# LCmeter0-LCD3310-8pinlcd-PIC-COMP.net
KiCad netlist of a schematic drawn in EAGLE
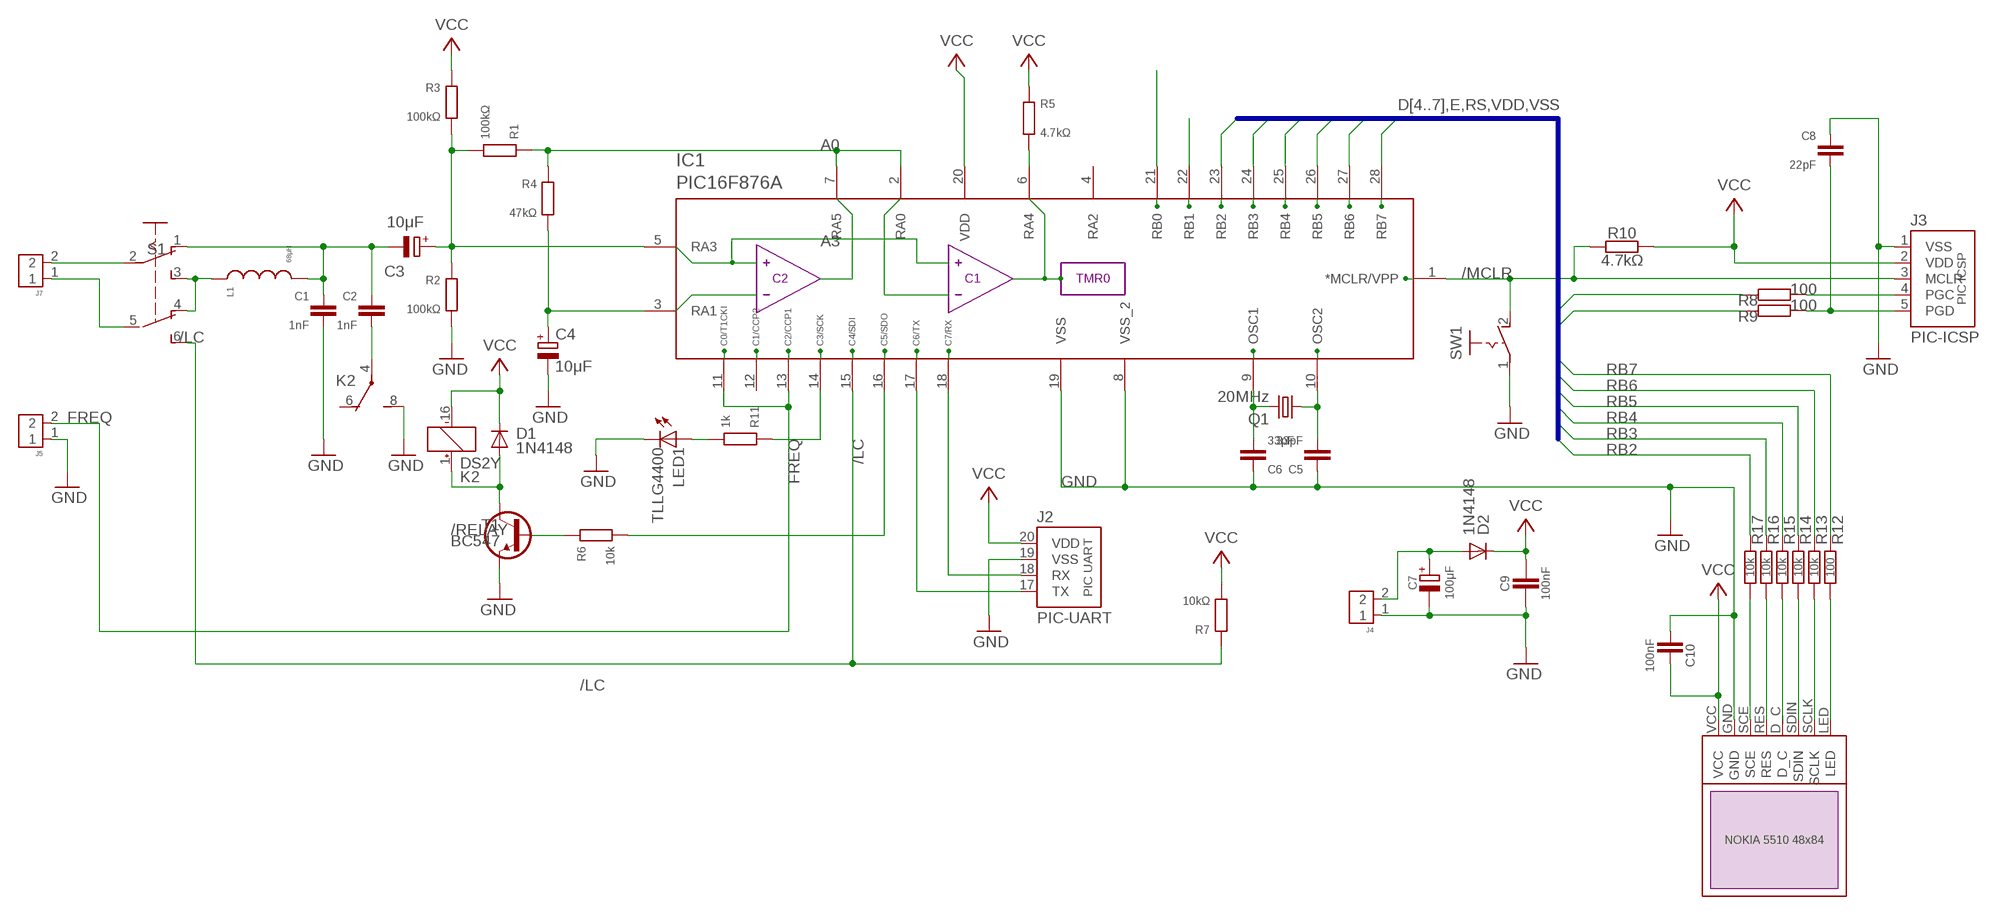
[diagram p0: schematic, sheet 1]

(export (version "E")
  (design (tool "Eeschema 10.0.6"))
  (components
    (comp (ref "C1")
      (value "1nF")
      (footprint "eagle-import:C050-025X060")
      (libsource (lib "eagle-import") (part "C025-025X060"))
    )
    (comp (ref "C2")
      (value "1nF")
      (footprint "eagle-import:C050-025X060")
      (libsource (lib "eagle-import") (part "C025-025X060"))
    )
    (comp (ref "C3")
      (value "10μF")
      (footprint "eagle-import:E2,5-4")
      (libsource (lib "eagle-import") (part "CPOLE2,5-4"))
    )
    (comp (ref "C4")
      (value "10μF")
      (footprint "eagle-import:E2,5-4")
      (libsource (lib "eagle-import") (part "CPOLE2,5-4"))
    )
    (comp (ref "C5")
      (value "33pF")
      (footprint "eagle-import:C025-020X036")
      (libsource (lib "eagle-import") (part "C025-020X036"))
    )
    (comp (ref "C6")
      (value "33pF")
      (footprint "eagle-import:C025-020X036")
      (libsource (lib "eagle-import") (part "C025-020X036"))
    )
    (comp (ref "C7")
      (value "100μF")
      (footprint "eagle-import:E5-5")
      (libsource (lib "eagle-import") (part "CPOLE5-5"))
    )
    (comp (ref "C8")
      (value "22pF")
      (footprint "eagle-import:C050-020X036")
      (libsource (lib "eagle-import") (part "C050-020X036"))
    )
    (comp (ref "C9")
      (value "100nF")
      (footprint "eagle-import:C025-024X044")
      (libsource (lib "eagle-import") (part "C-EU025-024X044"))
    )
    (comp (ref "C10")
      (value "100nF")
      (footprint "eagle-import:C025-015X024_V")
      (libsource (lib "eagle-import") (part "C025-015X024"))
    )
    (comp (ref "D1")
      (value "1N4148")
      (footprint "eagle-import:DO34-7")
      (libsource (lib "eagle-import") (part "1N414834-7"))
    )
    (comp (ref "D2")
      (value "1N4148")
      (footprint "eagle-import:DO34-10V")
      (libsource (lib "eagle-import") (part "1N414834-10V"))
    )
    (comp (ref "IC1")
      (value "PIC16F876A")
      (footprint "eagle-import:DIL28-3_V")
      (libsource (lib "eagle-import") (part "PIC16F876A-X/SP-COMPDIL28-3/V"))
    )
    (comp (ref "J2")
      (value "PIC-UART")
      (footprint "eagle-import:PIC-UART")
      (libsource (lib "eagle-import") (part "PIC-UART"))
    )
    (comp (ref "J3")
      (value "PIC-ICSP")
      (footprint "eagle-import:PIC-ICSP")
      (libsource (lib "eagle-import") (part "PIC-ICSPICSP"))
    )
    (comp (ref "J4")
      (value "J4")
      (footprint "eagle-import:CONN-2P")
      (libsource (lib "eagle-import") (part "CONN-2P2P/H"))
    )
    (comp (ref "J5")
      (value "CONN-2P2P/V")
      (footprint "eagle-import:CONN-2P-V")
      (libsource (lib "eagle-import") (part "CONN-2P2P/V"))
    )
    (comp (ref "J6")
      (value "NOKIA-5510-48X84")
      (footprint "eagle-import:CONN-LCD5510")
      (libsource (lib "eagle-import") (part "NOKIA-5510-48X84"))
    )
    (comp (ref "J7")
      (value "CONN-2P2P/V")
      (footprint "eagle-import:CONN-2P-V")
      (libsource (lib "eagle-import") (part "CONN-2P2P/V"))
    )
    (comp (ref "K2")
      (value "DS2Y")
      (footprint "eagle-import:DS2Y")
      (fields (field (name "MPN") "DS2Y-S-DC5V"))
      (libsource (lib "eagle-import") (part "DS2Y-S-DC5V"))
    )
    (comp (ref "L1")
      (value "68μH")
      (footprint "eagle-import:L-09R")
      (libsource (lib "eagle-import") (part "L-09R"))
    )
    (comp (ref "LED1")
      (value "TLLG4400")
      (footprint "eagle-import:LED3MM")
      (fields (field (name "MF") "VISHAY SEMICONDUCTOR"))
      (libsource (lib "eagle-import") (part "TLLG4400"))
    )
    (comp (ref "Q1")
      (value "20MHz")
      (footprint "eagle-import:HC49")
      (libsource (lib "eagle-import") (part "CRYSTALHC49"))
    )
    (comp (ref "R1")
      (value "100kΩ")
      (footprint "eagle-import:0202_7")
      (libsource (lib "eagle-import") (part "R0202/7"))
    )
    (comp (ref "R2")
      (value "100kΩ")
      (footprint "eagle-import:0202_7")
      (libsource (lib "eagle-import") (part "R0202/7"))
    )
    (comp (ref "R3")
      (value "100kΩ")
      (footprint "eagle-import:0202_7")
      (libsource (lib "eagle-import") (part "R0202/7"))
    )
    (comp (ref "R4")
      (value "47kΩ")
      (footprint "eagle-import:0202_7")
      (libsource (lib "eagle-import") (part "R0202/7"))
    )
    (comp (ref "R5")
      (value "4.7kΩ")
      (footprint "eagle-import:0202_7")
      (libsource (lib "eagle-import") (part "R0202/7"))
    )
    (comp (ref "R6")
      (value "10k")
      (footprint "eagle-import:0202_7-V")
      (libsource (lib "eagle-import") (part "R0202/7-V"))
    )
    (comp (ref "R7")
      (value "10kΩ")
      (footprint "eagle-import:0202_10-V")
      (libsource (lib "eagle-import") (part "R0202/10-V"))
    )
    (comp (ref "R8")
      (value "100")
      (footprint "eagle-import:0202_7")
      (libsource (lib "eagle-import") (part "R0202/7"))
    )
    (comp (ref "R9")
      (value "100")
      (footprint "eagle-import:0202_2V")
      (libsource (lib "eagle-import") (part "R0202/2V"))
    )
    (comp (ref "R10")
      (value "4.7kΩ")
      (footprint "eagle-import:0202_7")
      (libsource (lib "eagle-import") (part "R0202/7"))
    )
    (comp (ref "R11")
      (value "1k")
      (footprint "eagle-import:0202_5-V")
      (libsource (lib "eagle-import") (part "R0202/5-V"))
    )
    (comp (ref "R12")
      (value "100")
      (footprint "eagle-import:0202_7")
      (libsource (lib "eagle-import") (part "R0202/7"))
    )
    (comp (ref "R13")
      (value "10k")
      (footprint "eagle-import:0202_7")
      (libsource (lib "eagle-import") (part "R0202/7"))
    )
    (comp (ref "R14")
      (value "10k")
      (footprint "eagle-import:0202_7")
      (libsource (lib "eagle-import") (part "R0202/7"))
    )
    (comp (ref "R15")
      (value "10k")
      (footprint "eagle-import:0202_7")
      (libsource (lib "eagle-import") (part "R0202/7"))
    )
    (comp (ref "R16")
      (value "10k")
      (footprint "eagle-import:0202_7")
      (libsource (lib "eagle-import") (part "R0202/7"))
    )
    (comp (ref "R17")
      (value "10k")
      (footprint "eagle-import:0202_7")
      (libsource (lib "eagle-import") (part "R0202/7"))
    )
    (comp (ref "S1")
      (value "SL-SW-2P-2T-H")
      (footprint "eagle-import:SLSW-2P2T-H")
      (libsource (lib "eagle-import") (part "SL-SW-2P-2T-H"))
    )
    (comp (ref "SW1")
      (value "PB-1P-1T")
      (footprint "eagle-import:PB-1P1T")
      (libsource (lib "eagle-import") (part "PB-1P-1T"))
    )
    (comp (ref "T1")
      (value "BC547")
      (footprint "eagle-import:TO92-CBE-A")
      (libsource (lib "eagle-import") (part "BC547CBE-A"))
    )
  )
  (nets
    (net (code "5") (name "/A0") (class "Default")
      (node (ref "IC1") (pin "2") (pinfunction "RA0_2") (pintype "passive"))
      (node (ref "IC1") (pin "7") (pinfunction "RA5_7") (pintype "passive"))
      (node (ref "R1") (pin "2") (pinfunction "2_2") (pintype "passive"))
      (node (ref "R4") (pin "2") (pinfunction "2_2") (pintype "passive"))
    )
    (net (code "6") (name "/A3") (class "Default")
      (node (ref "C3") (pin "+") (pinfunction "+_+") (pintype "passive"))
      (node (ref "IC1") (pin "5") (pinfunction "RA3_5") (pintype "passive"))
      (node (ref "R1") (pin "1") (pinfunction "1_1") (pintype "passive"))
      (node (ref "R2") (pin "2") (pinfunction "2_2") (pintype "passive"))
      (node (ref "R3") (pin "1") (pinfunction "1_1") (pintype "passive"))
    )
    (net (code "7") (name "/FREQ") (class "Default")
      (node (ref "IC1") (pin "11") (pinfunction "RC0_11") (pintype "passive"))
      (node (ref "IC1") (pin "13") (pinfunction "RC2_13") (pintype "passive"))
      (node (ref "J5") (pin "2") (pinfunction "2_2") (pintype "bidirectional"))
    )
    (net (code "8") (name "/RB2") (class "Default")
      (node (ref "IC1") (pin "23") (pinfunction "RB2_23") (pintype "passive"))
      (node (ref "R17") (pin "2") (pinfunction "2_2") (pintype "passive"))
    )
    (net (code "9") (name "/RB3") (class "Default")
      (node (ref "IC1") (pin "24") (pinfunction "RB3_24") (pintype "passive"))
      (node (ref "R16") (pin "2") (pinfunction "2_2") (pintype "passive"))
    )
    (net (code "10") (name "/RB4") (class "Default")
      (node (ref "IC1") (pin "25") (pinfunction "RB4_25") (pintype "passive"))
      (node (ref "R15") (pin "2") (pinfunction "2_2") (pintype "passive"))
    )
    (net (code "11") (name "/RB5") (class "Default")
      (node (ref "IC1") (pin "26") (pinfunction "RB5_26") (pintype "passive"))
      (node (ref "R14") (pin "2") (pinfunction "2_2") (pintype "passive"))
    )
    (net (code "12") (name "/RB6") (class "Default")
      (node (ref "IC1") (pin "27") (pinfunction "RB6_27") (pintype "passive"))
      (node (ref "R13") (pin "2") (pinfunction "2_2") (pintype "passive"))
      (node (ref "R8") (pin "2") (pinfunction "2_2") (pintype "passive"))
    )
    (net (code "13") (name "/RB7") (class "Default")
      (node (ref "IC1") (pin "28") (pinfunction "RB7_28") (pintype "passive"))
      (node (ref "R12") (pin "2") (pinfunction "2_2") (pintype "passive"))
      (node (ref "R9") (pin "2") (pinfunction "2_2") (pintype "passive"))
    )
    (net (code "15") (name "/{slash}LC") (class "Default")
      (node (ref "IC1") (pin "15") (pinfunction "RC4_15") (pintype "passive"))
      (node (ref "R7") (pin "2") (pinfunction "2_2") (pintype "passive"))
      (node (ref "S1") (pin "6") (pinfunction "S1_6") (pintype "passive"))
    )
    (net (code "16") (name "/{slash}MCLR") (class "Default")
      (node (ref "IC1") (pin "1") (pinfunction "*MCLR/VPP_1") (pintype "passive"))
      (node (ref "J3") (pin "3") (pinfunction "MCLR_3") (pintype "passive"))
      (node (ref "R10") (pin "2") (pinfunction "2_2") (pintype "passive"))
      (node (ref "SW1") (pin "2") (pinfunction "S_2") (pintype "passive"))
    )
    (net (code "17") (name "/{slash}RELAY") (class "Default")
      (node (ref "D1") (pin "A") (pinfunction "A_A") (pintype "passive"))
      (node (ref "K2") (pin "1") (pinfunction "+_1") (pintype "passive"))
      (node (ref "T1") (pin "C") (pinfunction "C_C") (pintype "passive"))
    )
    (net (code "18") (name "GND") (class "Default")
      (node (ref "C1") (pin "2") (pinfunction "2_2") (pintype "passive"))
      (node (ref "C10") (pin "1") (pinfunction "1_1") (pintype "passive"))
      (node (ref "C4") (pin "-") (pinfunction "-_-") (pintype "passive"))
      (node (ref "C5") (pin "1") (pinfunction "1_1") (pintype "passive"))
      (node (ref "C6") (pin "1") (pinfunction "1_1") (pintype "passive"))
      (node (ref "C7") (pin "-") (pinfunction "-_-") (pintype "passive"))
      (node (ref "C8") (pin "1") (pinfunction "1_1") (pintype "passive"))
      (node (ref "C9") (pin "2") (pinfunction "2_2") (pintype "passive"))
      (node (ref "IC1") (pin "19") (pinfunction "VSS_19") (pintype "passive"))
      (node (ref "IC1") (pin "8") (pinfunction "VSS_2_8") (pintype "passive"))
      (node (ref "J2") (pin "19") (pinfunction "VSS_19") (pintype "passive"))
      (node (ref "J3") (pin "1") (pinfunction "VSS_1") (pintype "passive"))
      (node (ref "J4") (pin "1") (pinfunction "1_1") (pintype "bidirectional"))
      (node (ref "J5") (pin "1") (pinfunction "1_1") (pintype "bidirectional"))
      (node (ref "J6") (pin "GND") (pinfunction "GND_GND") (pintype "passive"))
      (node (ref "K2") (pin "8") (pinfunction "S_8") (pintype "passive"))
      (node (ref "LED1") (pin "K") (pinfunction "C_K") (pintype "passive"))
      (node (ref "R2") (pin "1") (pinfunction "1_1") (pintype "passive"))
      (node (ref "SW1") (pin "1") (pinfunction "P_1") (pintype "passive"))
      (node (ref "T1") (pin "E") (pinfunction "E_E") (pintype "passive"))
    )
    (net (code "19") (name "Net-(C7-Pad+)") (class "Default")
      (node (ref "C7") (pin "+") (pinfunction "+_+") (pintype "passive"))
      (node (ref "D2") (pin "A") (pinfunction "A_A") (pintype "passive"))
      (node (ref "J4") (pin "2") (pinfunction "2_2") (pintype "bidirectional"))
    )
    (net (code "20") (name "Net-(IC1-OSC1)") (class "Default")
      (node (ref "C6") (pin "2") (pinfunction "2_2") (pintype "passive"))
      (node (ref "IC1") (pin "9") (pinfunction "OSC1_9") (pintype "passive"))
      (node (ref "Q1") (pin "2") (pinfunction "2_2") (pintype "passive"))
    )
    (net (code "21") (name "Net-(IC1-OSC2)") (class "Default")
      (node (ref "C5") (pin "2") (pinfunction "2_2") (pintype "passive"))
      (node (ref "IC1") (pin "10") (pinfunction "OSC2_10") (pintype "passive"))
      (node (ref "Q1") (pin "1") (pinfunction "1_1") (pintype "passive"))
    )
    (net (code "22") (name "Net-(IC1-RA1)") (class "Default")
      (node (ref "C4") (pin "+") (pinfunction "+_+") (pintype "passive"))
      (node (ref "IC1") (pin "3") (pinfunction "RA1_3") (pintype "passive"))
      (node (ref "R4") (pin "1") (pinfunction "1_1") (pintype "passive"))
    )
    (net (code "23") (name "Net-(IC1-RA4)") (class "Default")
      (node (ref "IC1") (pin "6") (pinfunction "RA4_6") (pintype "passive"))
      (node (ref "R5") (pin "1") (pinfunction "1_1") (pintype "passive"))
    )
    (net (code "24") (name "Net-(IC1-RC3)") (class "Default")
      (node (ref "IC1") (pin "14") (pinfunction "RC3_14") (pintype "passive"))
      (node (ref "R11") (pin "2") (pinfunction "2_2") (pintype "passive"))
    )
    (net (code "25") (name "Net-(IC1-RC5)") (class "Default")
      (node (ref "IC1") (pin "16") (pinfunction "RC5_16") (pintype "passive"))
      (node (ref "R6") (pin "1") (pinfunction "1_1") (pintype "passive"))
    )
    (net (code "26") (name "Net-(IC1-RC6)") (class "Default")
      (node (ref "IC1") (pin "17") (pinfunction "RC6_17") (pintype "passive"))
      (node (ref "J2") (pin "17") (pinfunction "TX_17") (pintype "passive"))
    )
    (net (code "27") (name "Net-(IC1-RC7)") (class "Default")
      (node (ref "IC1") (pin "18") (pinfunction "RC7_18") (pintype "passive"))
      (node (ref "J2") (pin "18") (pinfunction "RX_18") (pintype "passive"))
    )
    (net (code "28") (name "Net-(J3-PGC)") (class "Default")
      (node (ref "J3") (pin "4") (pinfunction "PGC_4") (pintype "passive"))
      (node (ref "R8") (pin "1") (pinfunction "1_1") (pintype "passive"))
    )
    (net (code "29") (name "Net-(J3-PGD)") (class "Default")
      (node (ref "C8") (pin "2") (pinfunction "2_2") (pintype "passive"))
      (node (ref "J3") (pin "5") (pinfunction "PGD_5") (pintype "passive"))
      (node (ref "R9") (pin "1") (pinfunction "1_1") (pintype "passive"))
    )
    (net (code "30") (name "Net-(J6-PadD_C)") (class "Default")
      (node (ref "J6") (pin "D_C") (pinfunction "D_C_D_C") (pintype "passive"))
      (node (ref "R15") (pin "1") (pinfunction "1_1") (pintype "passive"))
    )
    (net (code "31") (name "Net-(J6-PadLED)") (class "Default")
      (node (ref "J6") (pin "LED") (pinfunction "LED_LED") (pintype "passive"))
      (node (ref "R12") (pin "1") (pinfunction "1_1") (pintype "passive"))
    )
    (net (code "32") (name "Net-(J6-PadRES)") (class "Default")
      (node (ref "J6") (pin "RES") (pinfunction "RES_RES") (pintype "passive"))
      (node (ref "R16") (pin "1") (pinfunction "1_1") (pintype "passive"))
    )
    (net (code "33") (name "Net-(J6-PadSCE)") (class "Default")
      (node (ref "J6") (pin "SCE") (pinfunction "SCE_SCE") (pintype "passive"))
      (node (ref "R17") (pin "1") (pinfunction "1_1") (pintype "passive"))
    )
    (net (code "34") (name "Net-(J6-PadSCLK)") (class "Default")
      (node (ref "J6") (pin "SCLK") (pinfunction "SCLK_SCLK") (pintype "passive"))
      (node (ref "R13") (pin "1") (pinfunction "1_1") (pintype "passive"))
    )
    (net (code "35") (name "Net-(J6-PadSDIN)") (class "Default")
      (node (ref "J6") (pin "SDIN") (pinfunction "SDIN_SDIN") (pintype "passive"))
      (node (ref "R14") (pin "1") (pinfunction "1_1") (pintype "passive"))
    )
    (net (code "36") (name "Net-(K2B-P)") (class "Default")
      (node (ref "C2") (pin "2") (pinfunction "2_2") (pintype "passive"))
      (node (ref "K2") (pin "4") (pinfunction "P_4") (pintype "passive"))
    )
    (net (code "37") (name "Net-(L1-1)") (class "Default")
      (node (ref "L1") (pin "P$1") (pinfunction "1_P$1") (pintype "passive"))
      (node (ref "S1") (pin "3") (pinfunction "S_3") (pintype "passive"))
      (node (ref "S1") (pin "4") (pinfunction "O1_4") (pintype "passive"))
    )
    (net (code "38") (name "Net-(L1-2)") (class "Default")
      (node (ref "C1") (pin "1") (pinfunction "1_1") (pintype "passive"))
      (node (ref "C2") (pin "1") (pinfunction "1_1") (pintype "passive"))
      (node (ref "C3") (pin "-") (pinfunction "-_-") (pintype "passive"))
      (node (ref "L1") (pin "P$2") (pinfunction "2_P$2") (pintype "passive"))
      (node (ref "S1") (pin "1") (pinfunction "O_1") (pintype "passive"))
    )
    (net (code "39") (name "Net-(LED1-PadA)") (class "Default")
      (node (ref "LED1") (pin "A") (pinfunction "A_A") (pintype "passive"))
      (node (ref "R11") (pin "1") (pinfunction "1_1") (pintype "passive"))
    )
    (net (code "40") (name "Net-(R6-Pad2)") (class "Default")
      (node (ref "R6") (pin "2") (pinfunction "2_2") (pintype "passive"))
      (node (ref "T1") (pin "B") (pinfunction "B_B") (pintype "passive"))
    )
    (net (code "41") (name "Net-(S1-P)") (class "Default")
      (node (ref "J7") (pin "2") (pinfunction "2_2") (pintype "bidirectional"))
      (node (ref "S1") (pin "2") (pinfunction "P_2") (pintype "passive"))
    )
    (net (code "42") (name "Net-(S1-P1)") (class "Default")
      (node (ref "J7") (pin "1") (pinfunction "1_1") (pintype "bidirectional"))
      (node (ref "S1") (pin "5") (pinfunction "P1_5") (pintype "passive"))
    )
    (net (code "43") (name "VCC") (class "Default")
      (node (ref "C10") (pin "2") (pinfunction "2_2") (pintype "passive"))
      (node (ref "C9") (pin "1") (pinfunction "1_1") (pintype "passive"))
      (node (ref "D1") (pin "C") (pinfunction "C_C") (pintype "passive"))
      (node (ref "D2") (pin "C") (pinfunction "C_C") (pintype "passive"))
      (node (ref "IC1") (pin "20") (pinfunction "VDD_20") (pintype "passive"))
      (node (ref "J2") (pin "20") (pinfunction "VDD_20") (pintype "passive"))
      (node (ref "J3") (pin "2") (pinfunction "VDD_2") (pintype "passive"))
      (node (ref "J6") (pin "VCC") (pinfunction "VCC_VCC") (pintype "passive"))
      (node (ref "K2") (pin "16") (pinfunction "-_16") (pintype "passive"))
      (node (ref "R10") (pin "1") (pinfunction "1_1") (pintype "passive"))
      (node (ref "R3") (pin "2") (pinfunction "2_2") (pintype "passive"))
      (node (ref "R5") (pin "2") (pinfunction "2_2") (pintype "passive"))
      (node (ref "R7") (pin "1") (pinfunction "1_1") (pintype "passive"))
    )
    (net (code "44") (name "unconnected-(IC1-RA2-Pad4)") (class "Default")
      (node (ref "IC1") (pin "4") (pinfunction "RA2_4") (pintype "passive"))
    )
    (net (code "45") (name "unconnected-(IC1-RB0-Pad21)") (class "Default")
      (node (ref "IC1") (pin "21") (pinfunction "RB0_21") (pintype "passive"))
    )
    (net (code "46") (name "unconnected-(IC1-RB1-Pad22)") (class "Default")
      (node (ref "IC1") (pin "22") (pinfunction "RB1_22") (pintype "passive"))
    )
    (net (code "47") (name "unconnected-(IC1-RC1-Pad12)") (class "Default")
      (node (ref "IC1") (pin "12") (pinfunction "RC1_12") (pintype "passive"))
    )
    (net (code "48") (name "unconnected-(K2B-O-Pad6)") (class "Default")
      (node (ref "K2") (pin "6") (pinfunction "O_6") (pintype "passive"))
    )
  )
)
